# laser-breakout.net
KiCad netlist of a schematic drawn in EAGLE
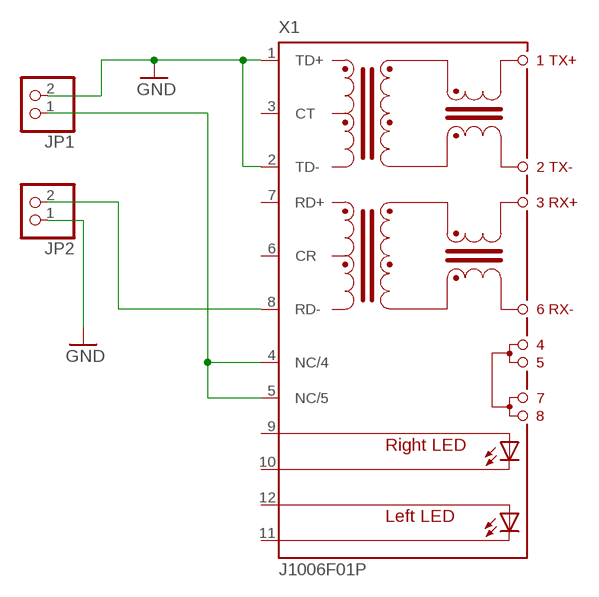
[diagram p0: schematic, sheet 1]

(export (version "E")
  (design (tool "Eeschema 10.0.6"))
  (components
    (comp (ref "JP1")
      (value "PINHD-1X2")
      (footprint "eagle-import:1X02")
      (libsource (lib "eagle-import") (part "PINHD-1X2"))
    )
    (comp (ref "JP2")
      (value "PINHD-1X2")
      (footprint "eagle-import:1X02")
      (libsource (lib "eagle-import") (part "PINHD-1X2"))
    )
    (comp (ref "X1")
      (value "J1006F01P")
      (footprint "eagle-import:J1")
      (libsource (lib "eagle-import") (part "J1006F01P"))
    )
  )
  (nets
    (net (code "1") (name "GND") (class "Default")
      (node (ref "JP1") (pin "2") (pinfunction "2_2") (pintype "passive"))
      (node (ref "JP2") (pin "1") (pinfunction "1_1") (pintype "passive"))
      (node (ref "X1") (pin "1") (pinfunction "TD+_1") (pintype "input"))
      (node (ref "X1") (pin "2") (pinfunction "TD-_2") (pintype "input"))
    )
    (net (code "2") (name "Net-(X1-NC{slash}4)") (class "Default")
      (node (ref "JP1") (pin "1") (pinfunction "1_1") (pintype "passive"))
      (node (ref "X1") (pin "4") (pinfunction "NC/4_4") (pintype "input"))
      (node (ref "X1") (pin "5") (pinfunction "NC/5_5") (pintype "input"))
    )
    (net (code "3") (name "Net-(X1-RD-)") (class "Default")
      (node (ref "JP2") (pin "2") (pinfunction "2_2") (pintype "passive"))
      (node (ref "X1") (pin "8") (pinfunction "RD-_8") (pintype "input"))
    )
    (net (code "4") (name "unconnected-(X1-A-L-Pad12)") (class "Default")
      (node (ref "X1") (pin "12") (pinfunction "A-L_12") (pintype "passive"))
    )
    (net (code "5") (name "unconnected-(X1-A-R-Pad9)") (class "Default")
      (node (ref "X1") (pin "9") (pinfunction "A-R_9") (pintype "passive"))
    )
    (net (code "6") (name "unconnected-(X1-C-L-Pad11)") (class "Default")
      (node (ref "X1") (pin "11") (pinfunction "C-L_11") (pintype "passive"))
    )
    (net (code "7") (name "unconnected-(X1-C-R-Pad10)") (class "Default")
      (node (ref "X1") (pin "10") (pinfunction "C-R_10") (pintype "passive"))
    )
    (net (code "8") (name "unconnected-(X1-CR-Pad6)") (class "Default")
      (node (ref "X1") (pin "6") (pinfunction "CR_6") (pintype "input"))
    )
    (net (code "9") (name "unconnected-(X1-CT-Pad3)") (class "Default")
      (node (ref "X1") (pin "3") (pinfunction "CT_3") (pintype "input"))
    )
    (net (code "10") (name "unconnected-(X1-RD+-Pad7)") (class "Default")
      (node (ref "X1") (pin "7") (pinfunction "RD+_7") (pintype "input"))
    )
  )
)
